# 09-AD9513-2.net
KiCad netlist of a schematic drawn in Altium Designer
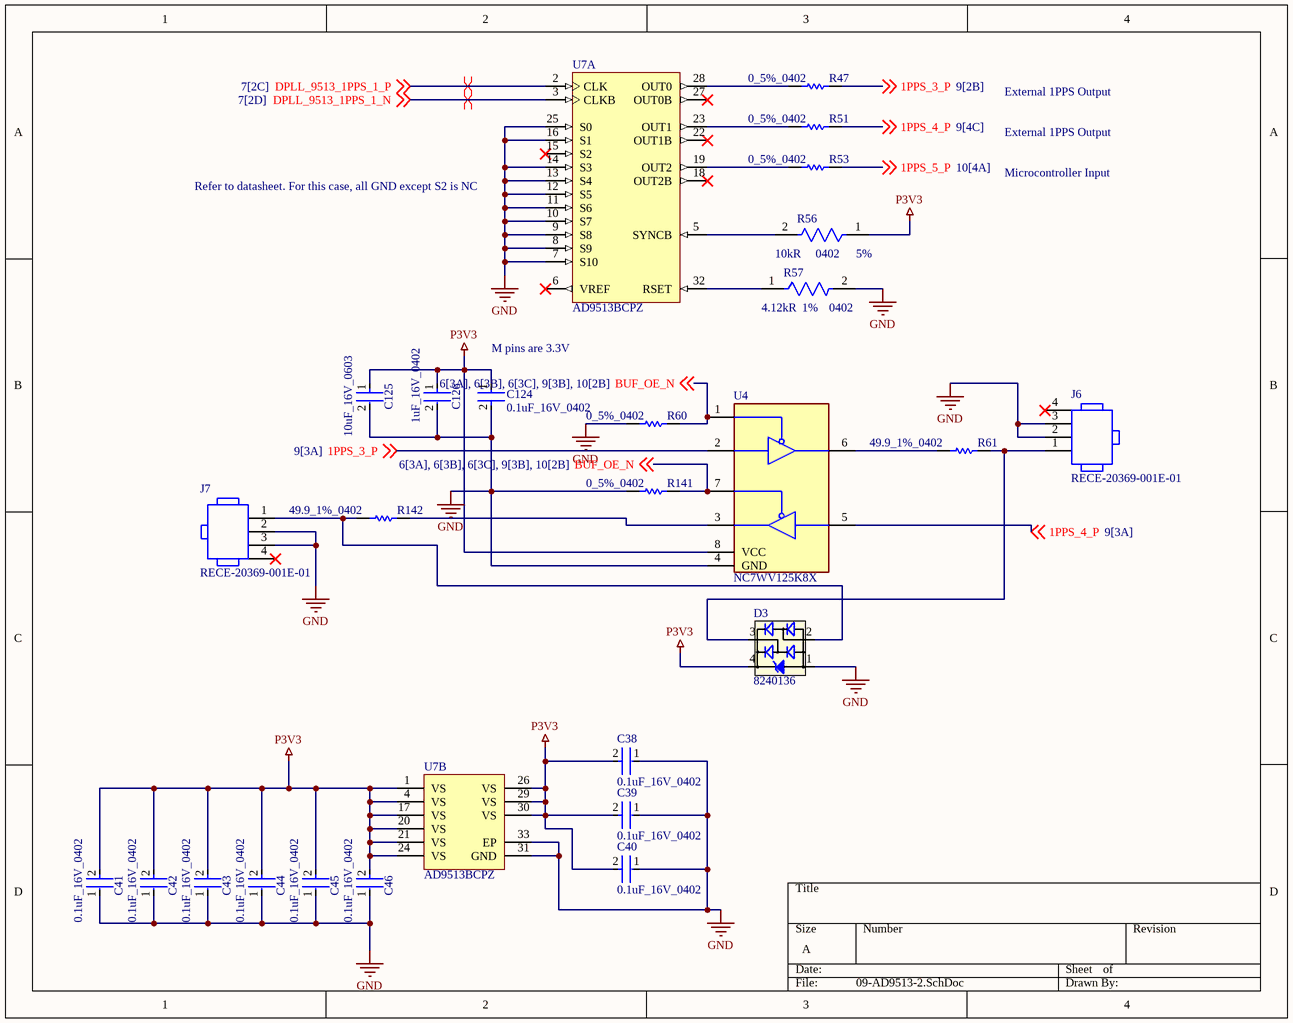
[diagram p0: 09-AD9513-2.SchDoc]

(export (version "E")
  (design (tool "Eeschema 10.0.6"))
  (components
    (comp (ref "C38")
      (value "0.1uF_16V_0402")
      (footprint "FP-GRM15-MFG")
      (description "CAP CER 0.1UF 16V X7R 0402")
      (fields (field (name "MANUFACTURER PART NUMBER") "GRM155R71C104KA88D") (field (name "TOLERANCE") "10%"))
      (libsource (lib "Altium Content Vault") (part "236180d848d6139a670b325ea6854c9"))
    )
    (comp (ref "C39")
      (value "0.1uF_16V_0402")
      (footprint "FP-GRM15-MFG")
      (description "CAP CER 0.1UF 16V X7R 0402")
      (fields (field (name "MANUFACTURER PART NUMBER") "GRM155R71C104KA88D") (field (name "TOLERANCE") "10%"))
      (libsource (lib "Altium Content Vault") (part "236180d848d6139a670b325ea6854c9"))
    )
    (comp (ref "C40")
      (value "0.1uF_16V_0402")
      (footprint "FP-GRM15-MFG")
      (description "CAP CER 0.1UF 16V X7R 0402")
      (fields (field (name "MANUFACTURER PART NUMBER") "GRM155R71C104KA88D") (field (name "TOLERANCE") "10%"))
      (libsource (lib "Altium Content Vault") (part "236180d848d6139a670b325ea6854c9"))
    )
    (comp (ref "C41")
      (value "0.1uF_16V_0402")
      (footprint "FP-GRM15-MFG")
      (description "CAP CER 0.1UF 16V X7R 0402")
      (fields (field (name "MANUFACTURER PART NUMBER") "GRM155R71C104KA88D") (field (name "TOLERANCE") "10%"))
      (libsource (lib "Altium Content Vault") (part "236180d848d6139a670b325ea6854c9"))
    )
    (comp (ref "C42")
      (value "0.1uF_16V_0402")
      (footprint "FP-GRM15-MFG")
      (description "CAP CER 0.1UF 16V X7R 0402")
      (fields (field (name "MANUFACTURER PART NUMBER") "GRM155R71C104KA88D") (field (name "TOLERANCE") "10%"))
      (libsource (lib "Altium Content Vault") (part "236180d848d6139a670b325ea6854c9"))
    )
    (comp (ref "C43")
      (value "0.1uF_16V_0402")
      (footprint "FP-GRM15-MFG")
      (description "CAP CER 0.1UF 16V X7R 0402")
      (fields (field (name "MANUFACTURER PART NUMBER") "GRM155R71C104KA88D") (field (name "TOLERANCE") "10%"))
      (libsource (lib "Altium Content Vault") (part "236180d848d6139a670b325ea6854c9"))
    )
    (comp (ref "C44")
      (value "0.1uF_16V_0402")
      (footprint "FP-GRM15-MFG")
      (description "CAP CER 0.1UF 16V X7R 0402")
      (fields (field (name "MANUFACTURER PART NUMBER") "GRM155R71C104KA88D") (field (name "TOLERANCE") "10%"))
      (libsource (lib "Altium Content Vault") (part "236180d848d6139a670b325ea6854c9"))
    )
    (comp (ref "C45")
      (value "0.1uF_16V_0402")
      (footprint "FP-GRM15-MFG")
      (description "CAP CER 0.1UF 16V X7R 0402")
      (fields (field (name "MANUFACTURER PART NUMBER") "GRM155R71C104KA88D") (field (name "TOLERANCE") "10%"))
      (libsource (lib "Altium Content Vault") (part "236180d848d6139a670b325ea6854c9"))
    )
    (comp (ref "C46")
      (value "0.1uF_16V_0402")
      (footprint "FP-GRM15-MFG")
      (description "CAP CER 0.1UF 16V X7R 0402")
      (fields (field (name "MANUFACTURER PART NUMBER") "GRM155R71C104KA88D") (field (name "TOLERANCE") "10%"))
      (libsource (lib "Altium Content Vault") (part "236180d848d6139a670b325ea6854c9"))
    )
    (comp (ref "C124")
      (value "GRM155R71C104KA88D")
      (footprint "FP-GRM15-MFG")
      (description "CAP CER 0.1UF 16V X7R 0402")
      (fields
        (field (name "TOLERANCE") "10%")
        (field (name "OCTOPART") "https://octopart.com/grm155r71c104ka88d-murata-196880")
        (field (name "DIGIKEY DESCRIPTION") "0.1uF_16V_0402")
      )
      (libsource (lib "Altium Content Vault") (part "236180d848d6139a670b325ea6854c9"))
    )
    (comp (ref "C125")
      (value "10uF_16V_0603")
      (footprint "FP-C1608-MFG")
      (description "CAP CER 10UF 16V X5R 0603")
      (fields
        (field (name "OCTOPART") "https://octopart.com/c1608x5r1c106m080ab-tdk-26013480")
        (field (name "MANUFACTURER") "TDK Corporation")
      )
      (libsource (lib "Altium Content Vault") (part "11868f565c42a9108669ba33697ecf6"))
    )
    (comp (ref "C126")
      (value "1uF_16V_0402")
      (footprint "FP-0402-L_1_0_0_05-W_0_5-IPC_C")
      (description "None")
      (fields (field (name "TOLERANCE") "20%") (field (name "VOLTAGE") "16V"))
      (libsource (lib "Altium Content Vault") (part "b4654b650e69147ec39a6b967a45e02"))
    )
    (comp (ref "D3")
      (value "8240136")
      (footprint "SOT143-4L")
      (description "TVS Diode WE-TVS-HS, VRWM=3.3V")
      (fields (field (name "MANUFACTURER") "Wuerth Elektronik"))
      (libsource (lib "Altium Content Vault") (part "WE-TVS-HS-4"))
    )
    (comp (ref "J6")
      (value "RECE-20369-001E-01")
      (footprint "TG-RECE-20369-001E-4_V")
      (description "RF Connector, Onboard Receptacle, IPEX MHFIII")
      (fields (field (name "MANUFACTURER") "Taoglas"))
      (libsource (lib "Altium Content Vault") (part "TG-RECE-20369-001E-01-4"))
    )
    (comp (ref "J7")
      (value "RECE-20369-001E-01")
      (footprint "TG-RECE-20369-001E-4_V")
      (description "RF Connector, Onboard Receptacle, IPEX MHFIII")
      (fields (field (name "MANUFACTURER") "Taoglas"))
      (libsource (lib "Altium Content Vault") (part "TG-RECE-20369-001E-01-4"))
    )
    (comp (ref "R47")
      (value "0_5%_0402")
      (footprint "RESC1005X40X25LL10T10")
      (fields (field (name "MANUFACTURER") "KOA Speer") (field (name "PART NUMBER") "RK73Z1ETTP"))
      (libsource (lib "Altium Content Vault") (part "RES"))
    )
    (comp (ref "R51")
      (value "0_5%_0402")
      (footprint "RESC1005X40X25LL10T10")
      (fields (field (name "MANUFACTURER") "KOA Speer") (field (name "PART NUMBER") "RK73Z1ETTP"))
      (libsource (lib "Altium Content Vault") (part "RES"))
    )
    (comp (ref "R53")
      (value "0_5%_0402")
      (footprint "RESC1005X40X25LL10T10")
      (fields (field (name "MANUFACTURER") "KOA Speer") (field (name "PART NUMBER") "RK73Z1ETTP"))
      (libsource (lib "Altium Content Vault") (part "RES"))
    )
    (comp (ref "R56")
      (value "CRCW040210K0JNED")
      (footprint "FP-CRCW0402-e3-IPC_B")
      (description "RES Thick Film, 10kΩ, 5%, 0.063W, 200ppm/°C, 0402")
      (fields
        (field (name "CASE/PACKAGE") "0402")
        (field (name "RESISTANCE") "10kR")
        (field (name "TOLERANCE") "5%")
      )
      (libsource (lib "Altium Content Vault") (part "1029c3af85768c4190bb7ad29bc67b5"))
    )
    (comp (ref "R57")
      (value "CRCW04024K12FKED")
      (footprint "FP-CRCW0402-e3-IPC_A")
      (description "RES Thick Film, 4.12kΩ, 1%, 0.063W, 100ppm/°C, 0402")
      (fields
        (field (name "RESISTANCE") "4.12kR")
        (field (name "CASE/PACKAGE") "0402")
        (field (name "TOLERANCE") "1%")
      )
      (libsource (lib "Altium Content Vault") (part "1029c3af85768c4190bb7ad29bc67b5"))
    )
    (comp (ref "R60")
      (value "0_5%_0402")
      (footprint "RESC1005X40X25LL10T10")
      (fields (field (name "MANUFACTURER") "KOA Speer") (field (name "PART NUMBER") "RK73Z1ETTP"))
      (libsource (lib "Altium Content Vault") (part "RES"))
    )
    (comp (ref "R61")
      (value "49.9_1%_0402")
      (footprint "RESC1005X40X25NL05T05")
      (fields (field (name "MANUFACTURER") "Panasonic") (field (name "PART NUMBER") "ERJ-2RKF49R9X"))
      (libsource (lib "Altium Content Vault") (part "RES"))
    )
    (comp (ref "R141")
      (value "0_5%_0402")
      (footprint "RESC1005X40X25LL10T10")
      (fields (field (name "MANUFACTURER") "KOA Speer") (field (name "PART NUMBER") "RK73Z1ETTP"))
      (libsource (lib "Altium Content Vault") (part "RES"))
    )
    (comp (ref "R142")
      (value "49.9_1%_0402")
      (footprint "RESC1005X40X25NL05T05")
      (fields (field (name "MANUFACTURER") "Panasonic") (field (name "PART NUMBER") "ERJ-2RKF49R9X"))
      (libsource (lib "Altium Content Vault") (part "RES"))
    )
    (comp (ref "U4")
      (value "NC7WV125K8X")
      (footprint "NC7WV125")
      (description "Integrated Circuit")
      (fields (field (name "MOUSER PART NUMBER") "512-NC7WV125K8X"))
      (libsource (lib "SamacSys") (part "NC7WV125K8X"))
    )
    (comp (ref "U7")
      (value "AD9513BCPZ")
      (footprint "ADI-CP-32-2_N")
      (fields (field (name "MANUFACTURER") "Analog Devices"))
      (libsource (lib "Altium Content Vault") (part "ADI-AD9513-CP-32-2"))
    )
  )
  (nets
    (net (code "1") (name "1PPS_3_P") (class "Default")
      (node (ref "R47") (pin "2") (pinfunction "2_2") (pintype "passive"))
      (node (ref "U4") (pin "2") (pintype "passive"))
    )
    (net (code "2") (name "1PPS_4_P") (class "Default")
      (node (ref "R51") (pin "2") (pinfunction "2_2") (pintype "passive"))
      (node (ref "U4") (pin "5") (pintype "passive"))
    )
    (net (code "3") (name "1PPS_5_P") (class "Default")
      (node (ref "R53") (pin "2") (pinfunction "2_2") (pintype "passive"))
    )
    (net (code "4") (name "BUF_OE_N") (class "Default")
      (node (ref "R141") (pin "2") (pinfunction "2_2") (pintype "passive"))
      (node (ref "R60") (pin "2") (pinfunction "2_2") (pintype "passive"))
      (node (ref "U4") (pin "1") (pintype "passive"))
      (node (ref "U4") (pin "7") (pintype "passive"))
    )
    (net (code "5") (name "DPLL_9513_1PPS_1_N") (class "Default")
      (node (ref "U7") (pin "3") (pinfunction "CLKB_3") (pintype "input"))
    )
    (net (code "6") (name "DPLL_9513_1PPS_1_P") (class "Default")
      (node (ref "U7") (pin "2") (pinfunction "CLK_2") (pintype "input"))
    )
    (net (code "7") (name "GND") (class "Default")
      (node (ref "C124") (pin "2") (pinfunction "2_2") (pintype "passive"))
      (node (ref "C125") (pin "2") (pinfunction "2_2") (pintype "passive"))
      (node (ref "C126") (pin "2") (pinfunction "2_2") (pintype "passive"))
      (node (ref "C38") (pin "1") (pinfunction "1_1") (pintype "passive"))
      (node (ref "C39") (pin "1") (pinfunction "1_1") (pintype "passive"))
      (node (ref "C40") (pin "1") (pinfunction "1_1") (pintype "passive"))
      (node (ref "C41") (pin "1") (pinfunction "1_1") (pintype "passive"))
      (node (ref "C42") (pin "1") (pinfunction "1_1") (pintype "passive"))
      (node (ref "C43") (pin "1") (pinfunction "1_1") (pintype "passive"))
      (node (ref "C44") (pin "1") (pinfunction "1_1") (pintype "passive"))
      (node (ref "C45") (pin "1") (pinfunction "1_1") (pintype "passive"))
      (node (ref "C46") (pin "1") (pinfunction "1_1") (pintype "passive"))
      (node (ref "D3") (pin "1") (pinfunction "GND_1") (pintype "passive"))
      (node (ref "J6") (pin "2") (pinfunction "2_2") (pintype "passive"))
      (node (ref "J6") (pin "3") (pinfunction "3_3") (pintype "passive"))
      (node (ref "J7") (pin "2") (pinfunction "2_2") (pintype "passive"))
      (node (ref "J7") (pin "3") (pinfunction "3_3") (pintype "passive"))
      (node (ref "R141") (pin "1") (pinfunction "1_1") (pintype "passive"))
      (node (ref "R57") (pin "2") (pinfunction "2_2") (pintype "passive"))
      (node (ref "R60") (pin "1") (pinfunction "1_1") (pintype "passive"))
      (node (ref "U4") (pin "4") (pinfunction "GND_4") (pintype "passive"))
      (node (ref "U7") (pin "10") (pinfunction "S7_10") (pintype "input"))
      (node (ref "U7") (pin "11") (pinfunction "S6_11") (pintype "input"))
      (node (ref "U7") (pin "12") (pinfunction "S5_12") (pintype "input"))
      (node (ref "U7") (pin "13") (pinfunction "S4_13") (pintype "input"))
      (node (ref "U7") (pin "14") (pinfunction "S3_14") (pintype "input"))
      (node (ref "U7") (pin "16") (pinfunction "S1_16") (pintype "input"))
      (node (ref "U7") (pin "25") (pinfunction "S0_25") (pintype "input"))
      (node (ref "U7") (pin "31") (pinfunction "GND_31") (pintype "power_in"))
      (node (ref "U7") (pin "33") (pinfunction "EP_33") (pintype "power_in"))
      (node (ref "U7") (pin "7") (pinfunction "S10_7") (pintype "input"))
      (node (ref "U7") (pin "8") (pinfunction "S9_8") (pintype "input"))
      (node (ref "U7") (pin "9") (pinfunction "S8_9") (pintype "input"))
    )
    (net (code "8") (name "Net-(D3-I{slash}O1)") (class "Default")
      (node (ref "D3") (pin "2") (pinfunction "I/O1_2") (pintype "passive"))
      (node (ref "J7") (pin "1") (pinfunction "1_1") (pintype "passive"))
      (node (ref "R142") (pin "2") (pinfunction "2_2") (pintype "passive"))
    )
    (net (code "9") (name "Net-(D3-I{slash}O2)") (class "Default")
      (node (ref "D3") (pin "3") (pinfunction "I/O2_3") (pintype "passive"))
      (node (ref "J6") (pin "1") (pinfunction "1_1") (pintype "passive"))
      (node (ref "R61") (pin "1") (pinfunction "1_1") (pintype "passive"))
    )
    (net (code "10") (name "Net-(R61-Pad2)") (class "Default")
      (node (ref "R61") (pin "2") (pinfunction "2_2") (pintype "passive"))
      (node (ref "U4") (pin "6") (pintype "passive"))
    )
    (net (code "11") (name "Net-(R142-Pad1)") (class "Default")
      (node (ref "R142") (pin "1") (pinfunction "1_1") (pintype "passive"))
      (node (ref "U4") (pin "3") (pintype "passive"))
    )
    (net (code "12") (name "Net-(U7A-OUT0)") (class "Default")
      (node (ref "R47") (pin "1") (pinfunction "1_1") (pintype "passive"))
      (node (ref "U7") (pin "28") (pinfunction "OUT0_28") (pintype "output"))
    )
    (net (code "13") (name "Net-(U7A-OUT1)") (class "Default")
      (node (ref "R51") (pin "1") (pinfunction "1_1") (pintype "passive"))
      (node (ref "U7") (pin "23") (pinfunction "OUT1_23") (pintype "output"))
    )
    (net (code "14") (name "Net-(U7A-OUT2)") (class "Default")
      (node (ref "R53") (pin "1") (pinfunction "1_1") (pintype "passive"))
      (node (ref "U7") (pin "19") (pinfunction "OUT2_19") (pintype "output"))
    )
    (net (code "15") (name "Net-(U7A-RSET)") (class "Default")
      (node (ref "R57") (pin "1") (pinfunction "1_1") (pintype "passive"))
      (node (ref "U7") (pin "32") (pinfunction "RSET_32") (pintype "input"))
    )
    (net (code "16") (name "Net-(U7A-SYNCB)") (class "Default")
      (node (ref "R56") (pin "2") (pinfunction "2_2") (pintype "passive"))
      (node (ref "U7") (pin "5") (pinfunction "SYNCB_5") (pintype "input"))
    )
    (net (code "17") (name "P3V3") (class "Default")
      (node (ref "C124") (pin "1") (pinfunction "1_1") (pintype "passive"))
      (node (ref "C125") (pin "1") (pinfunction "1_1") (pintype "passive"))
      (node (ref "C126") (pin "1") (pinfunction "1_1") (pintype "passive"))
      (node (ref "C38") (pin "2") (pinfunction "2_2") (pintype "passive"))
      (node (ref "C39") (pin "2") (pinfunction "2_2") (pintype "passive"))
      (node (ref "C40") (pin "2") (pinfunction "2_2") (pintype "passive"))
      (node (ref "C41") (pin "2") (pinfunction "2_2") (pintype "passive"))
      (node (ref "C42") (pin "2") (pinfunction "2_2") (pintype "passive"))
      (node (ref "C43") (pin "2") (pinfunction "2_2") (pintype "passive"))
      (node (ref "C44") (pin "2") (pinfunction "2_2") (pintype "passive"))
      (node (ref "C45") (pin "2") (pinfunction "2_2") (pintype "passive"))
      (node (ref "C46") (pin "2") (pinfunction "2_2") (pintype "passive"))
      (node (ref "D3") (pin "4") (pinfunction "VDD_4") (pintype "passive"))
      (node (ref "R56") (pin "1") (pinfunction "1_1") (pintype "passive"))
      (node (ref "U4") (pin "8") (pinfunction "VCC_8") (pintype "passive"))
      (node (ref "U7") (pin "1") (pinfunction "VS_1") (pintype "power_in"))
      (node (ref "U7") (pin "17") (pinfunction "VS_17") (pintype "power_in"))
      (node (ref "U7") (pin "20") (pinfunction "VS_20") (pintype "power_in"))
      (node (ref "U7") (pin "21") (pinfunction "VS_21") (pintype "power_in"))
      (node (ref "U7") (pin "24") (pinfunction "VS_24") (pintype "power_in"))
      (node (ref "U7") (pin "26") (pinfunction "VS_26") (pintype "power_in"))
      (node (ref "U7") (pin "29") (pinfunction "VS_29") (pintype "power_in"))
      (node (ref "U7") (pin "30") (pinfunction "VS_30") (pintype "power_in"))
      (node (ref "U7") (pin "4") (pinfunction "VS_4") (pintype "power_in"))
    )
    (net (code "18") (name "unconnected-(J6-Pad4)") (class "Default")
      (node (ref "J6") (pin "4") (pinfunction "4_4") (pintype "passive+no_connect"))
    )
    (net (code "19") (name "unconnected-(J7-Pad4)") (class "Default")
      (node (ref "J7") (pin "4") (pinfunction "4_4") (pintype "passive+no_connect"))
    )
    (net (code "20") (name "unconnected-(U7A-OUT0B-Pad27)") (class "Default")
      (node (ref "U7") (pin "27") (pinfunction "OUT0B_27") (pintype "output+no_connect"))
    )
    (net (code "21") (name "unconnected-(U7A-OUT1B-Pad22)") (class "Default")
      (node (ref "U7") (pin "22") (pinfunction "OUT1B_22") (pintype "output+no_connect"))
    )
    (net (code "22") (name "unconnected-(U7A-OUT2B-Pad18)") (class "Default")
      (node (ref "U7") (pin "18") (pinfunction "OUT2B_18") (pintype "output+no_connect"))
    )
    (net (code "23") (name "unconnected-(U7A-S2-Pad15)") (class "Default")
      (node (ref "U7") (pin "15") (pinfunction "S2_15") (pintype "input+no_connect"))
    )
    (net (code "24") (name "unconnected-(U7A-VREF-Pad6)") (class "Default")
      (node (ref "U7") (pin "6") (pinfunction "VREF_6") (pintype "output+no_connect"))
    )
  )
)
